# air_flow.net
KiCad netlist of a schematic drawn in EAGLE
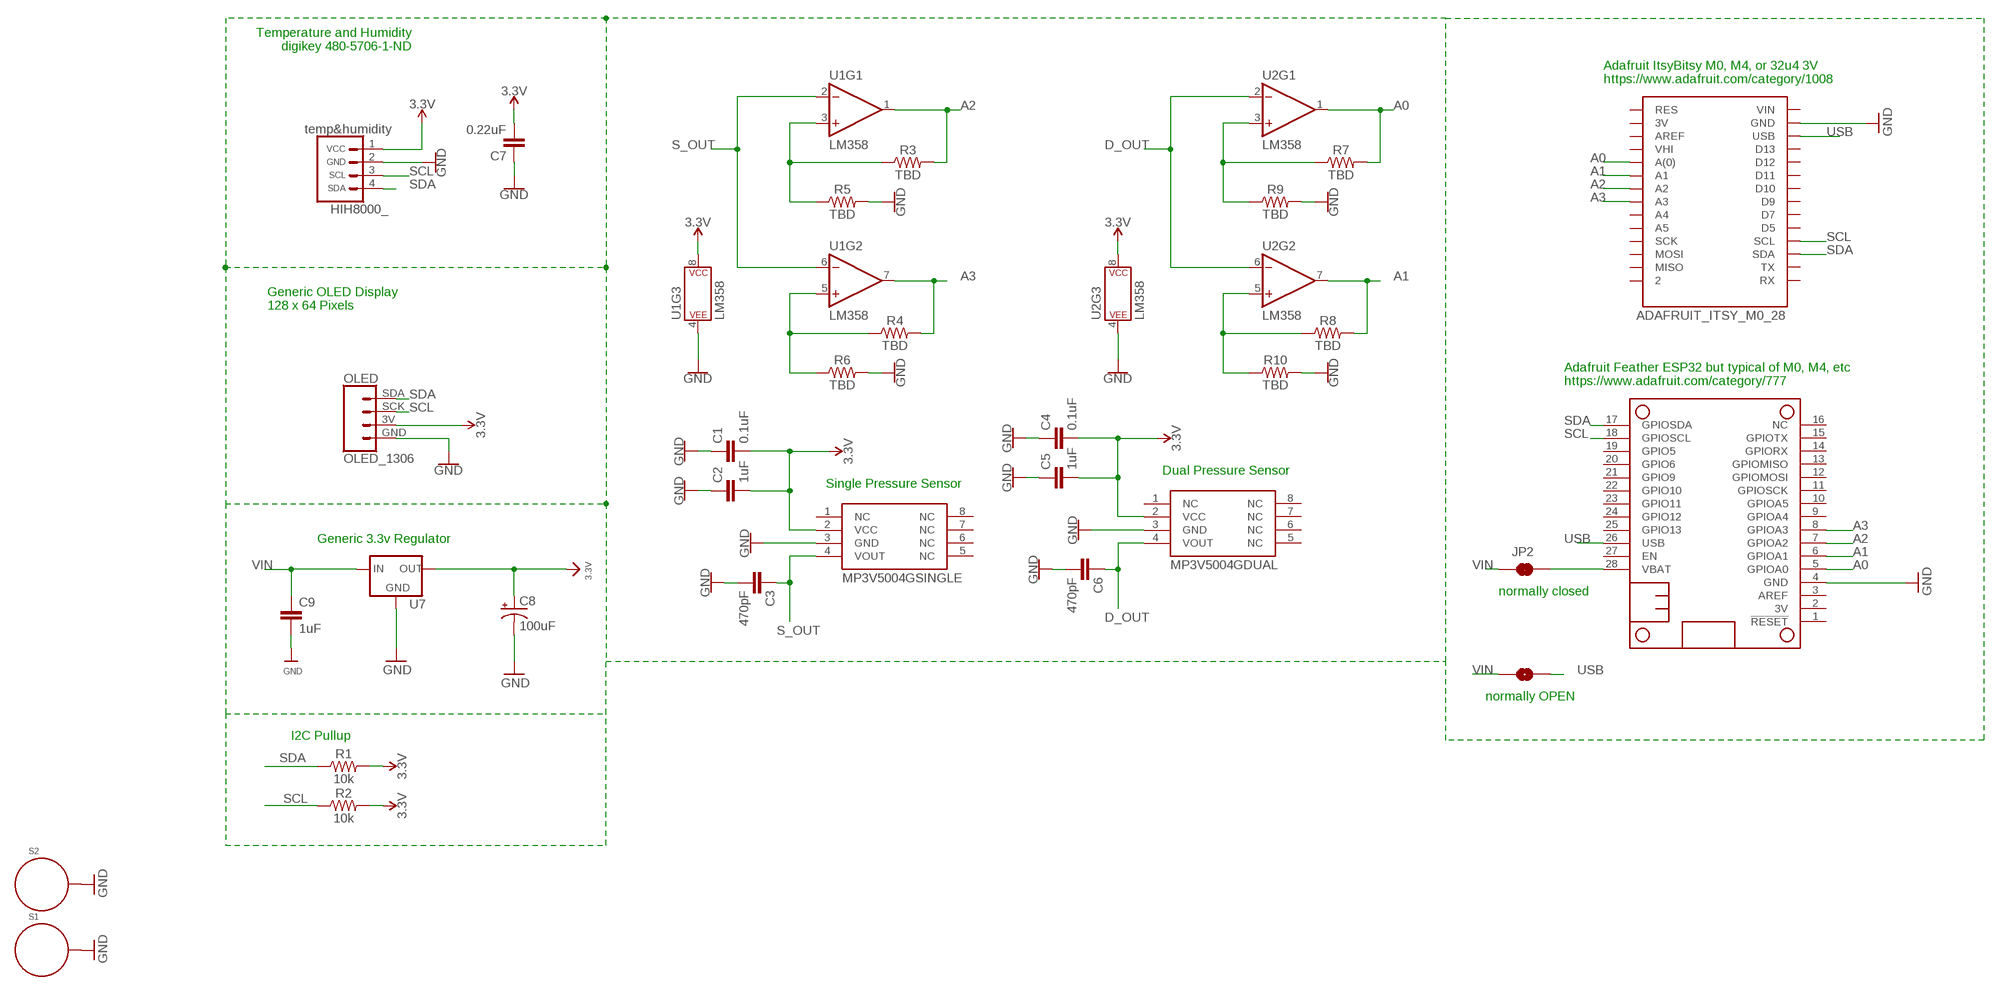
[diagram p0: schematic, sheet 1]

(export (version "E")
  (design (tool "Eeschema 10.0.6"))
  (components
    (comp (ref "C1")
      (value "0.1uF")
      (footprint "eagle-import:CAP-PTH-SMALL-KIT")
      (libsource (lib "eagle-import") (part "0.1UF-KIT-EZ-50V-20%"))
    )
    (comp (ref "C2")
      (value "1uF")
      (footprint "eagle-import:CAP-PTH-SMALL-KIT")
      (libsource (lib "eagle-import") (part "0.1UF-KIT-EZ-50V-20%"))
    )
    (comp (ref "C3")
      (value "470pF")
      (footprint "eagle-import:CAP-PTH-SMALL-KIT")
      (libsource (lib "eagle-import") (part "0.1UF-KIT-EZ-50V-20%"))
    )
    (comp (ref "C4")
      (value "0.1uF")
      (footprint "eagle-import:CAP-PTH-SMALL-KIT")
      (libsource (lib "eagle-import") (part "0.1UF-KIT-EZ-50V-20%"))
    )
    (comp (ref "C5")
      (value "1uF")
      (footprint "eagle-import:CAP-PTH-SMALL-KIT")
      (libsource (lib "eagle-import") (part "0.1UF-KIT-EZ-50V-20%"))
    )
    (comp (ref "C6")
      (value "470pF")
      (footprint "eagle-import:CAP-PTH-SMALL-KIT")
      (libsource (lib "eagle-import") (part "0.1UF-KIT-EZ-50V-20%"))
    )
    (comp (ref "C7")
      (value "0.22uF")
      (footprint "eagle-import:CAP-PTH-SMALL-KIT")
      (libsource (lib "eagle-import") (part "0.1UF-KIT-EZ-50V-20%"))
    )
    (comp (ref "C8")
      (value "100uF")
      (footprint "eagle-import:E3,5-8")
      (libsource (lib "eagle-import") (part "CPOL-USE3.5-8"))
    )
    (comp (ref "C9")
      (value "1uF")
      (footprint "eagle-import:CAP-PTH-SMALL-KIT")
      (libsource (lib "eagle-import") (part "0.1UF-KIT-EZ-50V-20%"))
    )
    (comp (ref "JP1")
      (value "JUMPER-SMT_2_NO_NO-SILK")
      (footprint "eagle-import:SMT-JUMPER_2_NO_NO-SILK")
      (libsource (lib "eagle-import") (part "JUMPER-SMT_2_NO_NO-SILK"))
    )
    (comp (ref "JP2")
      (value "JUMPER-SMT_2_NC_TRACE_SILK")
      (footprint "eagle-import:SMT-JUMPER_2_NC_TRACE_SILK")
      (libsource (lib "eagle-import") (part "JUMPER-SMT_2_NC_TRACE_SILK"))
    )
    (comp (ref "MS2")
      (value "FEATHERWING_NODIM")
      (footprint "eagle-import:FEATHERWING_DIM")
      (libsource (lib "eagle-import") (part "FEATHERWING_NODIM"))
    )
    (comp (ref "R1")
      (value "10k")
      (footprint "eagle-import:AXIAL-0.3")
      (libsource (lib "eagle-import") (part "10KOHM-HORIZ-1/4W-5%"))
    )
    (comp (ref "R2")
      (value "10k")
      (footprint "eagle-import:AXIAL-0.3")
      (libsource (lib "eagle-import") (part "10KOHM-HORIZ-1/4W-5%"))
    )
    (comp (ref "R3")
      (value "TBD")
      (footprint "eagle-import:AXIAL-0.3")
      (libsource (lib "eagle-import") (part "10KOHM-HORIZ-1/4W-5%"))
    )
    (comp (ref "R4")
      (value "TBD")
      (footprint "eagle-import:AXIAL-0.3")
      (libsource (lib "eagle-import") (part "10KOHM-HORIZ-1/4W-5%"))
    )
    (comp (ref "R5")
      (value "TBD")
      (footprint "eagle-import:AXIAL-0.3")
      (libsource (lib "eagle-import") (part "10KOHM-HORIZ-1/4W-5%"))
    )
    (comp (ref "R6")
      (value "TBD")
      (footprint "eagle-import:AXIAL-0.3")
      (libsource (lib "eagle-import") (part "10KOHM-HORIZ-1/4W-5%"))
    )
    (comp (ref "R7")
      (value "TBD")
      (footprint "eagle-import:AXIAL-0.3")
      (libsource (lib "eagle-import") (part "10KOHM-HORIZ-1/4W-5%"))
    )
    (comp (ref "R8")
      (value "TBD")
      (footprint "eagle-import:AXIAL-0.3")
      (libsource (lib "eagle-import") (part "10KOHM-HORIZ-1/4W-5%"))
    )
    (comp (ref "R9")
      (value "TBD")
      (footprint "eagle-import:AXIAL-0.3")
      (libsource (lib "eagle-import") (part "10KOHM-HORIZ-1/4W-5%"))
    )
    (comp (ref "R10")
      (value "TBD")
      (footprint "eagle-import:AXIAL-0.3")
      (libsource (lib "eagle-import") (part "10KOHM-HORIZ-1/4W-5%"))
    )
    (comp (ref "S1")
      (value "STANDOFF_ELECTRICAL5-32")
      (footprint "eagle-import:STANDOFF_ELECTRICAL_5_32")
      (libsource (lib "eagle-import") (part "STANDOFF_ELECTRICAL5-32"))
    )
    (comp (ref "S2")
      (value "STANDOFF_ELECTRICAL5-32")
      (footprint "eagle-import:STANDOFF_ELECTRICAL_5_32")
      (libsource (lib "eagle-import") (part "STANDOFF_ELECTRICAL5-32"))
    )
    (comp (ref "U$1")
      (value "OLED_1306")
      (footprint "eagle-import:OLED_1306")
      (libsource (lib "eagle-import") (part "OLED_1306"))
    )
    (comp (ref "U$2")
      (value "MP3V5004GSINGLE")
      (footprint "eagle-import:MP3V5004GP")
      (libsource (lib "eagle-import") (part "MP3V5004GSINGLE"))
    )
    (comp (ref "U$3")
      (value "MP3V5004GDUAL")
      (footprint "eagle-import:MP3V5004DP")
      (libsource (lib "eagle-import") (part "MP3V5004GDUAL"))
    )
    (comp (ref "U$4")
      (value "HIH8000_")
      (footprint "eagle-import:HIH8120_TH")
      (libsource (lib "eagle-import") (part "HIH8000_"))
    )
    (comp (ref "U$45")
      (value "ADAFRUIT_ITSY_M0_28")
      (footprint "eagle-import:ADAFRUIT_ITS_MO_28")
      (libsource (lib "eagle-import") (part "ADAFRUIT_ITSY_M0_28"))
    )
    (comp (ref "U1")
      (value "LM358")
      (footprint "eagle-import:DIP08")
      (libsource (lib "eagle-import") (part "LM358"))
    )
    (comp (ref "U2")
      (value "LM358")
      (footprint "eagle-import:DIP08")
      (libsource (lib "eagle-import") (part "LM358"))
    )
    (comp (ref "U7")
      (value "V_REG_78XXSINK")
      (footprint "eagle-import:TO220-IGO")
      (libsource (lib "eagle-import") (part "V_REG_78XXSINK"))
    )
  )
  (nets
    (net (code "1") (name "/3V") (class "Default")
      (node (ref "MS2") (pin "2") (pinfunction "3V_2") (pintype "power_in"))
    )
    (net (code "2") (name "/A0") (class "Default")
      (node (ref "MS2") (pin "5") (pinfunction "GPIOA0_5") (pintype "bidirectional"))
      (node (ref "R7") (pin "P$2") (pinfunction "2_P$2") (pintype "passive"))
      (node (ref "U$45") (pin "A0") (pinfunction "A(0)_A0") (pintype "bidirectional"))
      (node (ref "U2") (pin "1") (pinfunction "OUT_1") (pintype "output"))
    )
    (net (code "3") (name "/A1") (class "Default")
      (node (ref "MS2") (pin "6") (pinfunction "GPIOA1_6") (pintype "bidirectional"))
      (node (ref "R8") (pin "P$2") (pinfunction "2_P$2") (pintype "passive"))
      (node (ref "U$45") (pin "A1") (pinfunction "A1_A1") (pintype "bidirectional"))
      (node (ref "U2") (pin "7") (pinfunction "OUT_7") (pintype "output"))
    )
    (net (code "4") (name "/A2") (class "Default")
      (node (ref "MS2") (pin "7") (pinfunction "GPIOA2_7") (pintype "bidirectional"))
      (node (ref "R3") (pin "P$2") (pinfunction "2_P$2") (pintype "passive"))
      (node (ref "U$45") (pin "A2") (pinfunction "A2_A2") (pintype "bidirectional"))
      (node (ref "U1") (pin "1") (pinfunction "OUT_1") (pintype "output"))
    )
    (net (code "5") (name "/A3") (class "Default")
      (node (ref "MS2") (pin "8") (pinfunction "GPIOA3_8") (pintype "bidirectional"))
      (node (ref "R4") (pin "P$2") (pinfunction "2_P$2") (pintype "passive"))
      (node (ref "U$45") (pin "A3") (pinfunction "A3_A3") (pintype "bidirectional"))
      (node (ref "U1") (pin "7") (pinfunction "OUT_7") (pintype "output"))
    )
    (net (code "6") (name "/D_OUT") (class "Default")
      (node (ref "C6") (pin "1") (pinfunction "1_1") (pintype "passive"))
      (node (ref "U$3") (pin "4") (pinfunction "VOUT_4") (pintype "bidirectional"))
      (node (ref "U2") (pin "2") (pinfunction "-IN_2") (pintype "input"))
      (node (ref "U2") (pin "6") (pinfunction "-IN_6") (pintype "input"))
    )
    (net (code "7") (name "/SCL") (class "Default")
      (node (ref "MS2") (pin "18") (pinfunction "GPIOSCL_18") (pintype "bidirectional"))
      (node (ref "R2") (pin "P$1") (pinfunction "1_P$1") (pintype "passive"))
      (node (ref "U$1") (pin "SCK") (pinfunction "SCK_SCK") (pintype "passive"))
      (node (ref "U$4") (pin "3") (pinfunction "SCL_3") (pintype "power_in"))
      (node (ref "U$45") (pin "SCL") (pinfunction "SCL_SCL") (pintype "bidirectional"))
    )
    (net (code "8") (name "/SDA") (class "Default")
      (node (ref "MS2") (pin "17") (pinfunction "GPIOSDA_17") (pintype "bidirectional"))
      (node (ref "R1") (pin "P$1") (pinfunction "1_P$1") (pintype "passive"))
      (node (ref "U$1") (pin "SDA") (pinfunction "SDA_SDA") (pintype "passive"))
      (node (ref "U$4") (pin "4") (pinfunction "SDA_4") (pintype "passive"))
      (node (ref "U$45") (pin "SDA") (pinfunction "SDA_SDA") (pintype "bidirectional"))
    )
    (net (code "9") (name "/S_OUT") (class "Default")
      (node (ref "C3") (pin "1") (pinfunction "1_1") (pintype "passive"))
      (node (ref "U$2") (pin "4") (pinfunction "VOUT_4") (pintype "bidirectional"))
      (node (ref "U1") (pin "2") (pinfunction "-IN_2") (pintype "input"))
      (node (ref "U1") (pin "6") (pinfunction "-IN_6") (pintype "input"))
    )
    (net (code "10") (name "/USB") (class "Default")
      (node (ref "JP1") (pin "2") (pinfunction "2_2") (pintype "passive"))
      (node (ref "MS2") (pin "26") (pinfunction "USB_26") (pintype "power_in"))
      (node (ref "U$45") (pin "USB") (pinfunction "USB_USB") (pintype "bidirectional"))
    )
    (net (code "11") (name "/VIN") (class "Default")
      (node (ref "C9") (pin "1") (pinfunction "1_1") (pintype "passive"))
      (node (ref "JP2") (pin "1") (pinfunction "1_1") (pintype "passive"))
      (node (ref "U7") (pin "IN") (pinfunction "IN_IN") (pintype "input"))
    )
    (net (code "12") (name "3.3V") (class "Default")
      (node (ref "C1") (pin "2") (pinfunction "2_2") (pintype "passive"))
      (node (ref "C2") (pin "2") (pinfunction "2_2") (pintype "passive"))
      (node (ref "C4") (pin "2") (pinfunction "2_2") (pintype "passive"))
      (node (ref "C5") (pin "2") (pinfunction "2_2") (pintype "passive"))
      (node (ref "C7") (pin "2") (pinfunction "2_2") (pintype "passive"))
      (node (ref "C8") (pin "+") (pinfunction "+_+") (pintype "passive"))
      (node (ref "R1") (pin "P$2") (pinfunction "2_P$2") (pintype "passive"))
      (node (ref "R2") (pin "P$2") (pinfunction "2_P$2") (pintype "passive"))
      (node (ref "U$1") (pin "3V") (pinfunction "VCC_3V") (pintype "power_in"))
      (node (ref "U$2") (pin "2") (pinfunction "VCC_2") (pintype "bidirectional"))
      (node (ref "U$3") (pin "2") (pinfunction "VCC_2") (pintype "bidirectional"))
      (node (ref "U$4") (pin "1") (pinfunction "VCC_1") (pintype "passive"))
      (node (ref "U1") (pin "8") (pinfunction "P$V+_8") (pintype "bidirectional"))
      (node (ref "U2") (pin "8") (pinfunction "P$V+_8") (pintype "bidirectional"))
      (node (ref "U7") (pin "OUT") (pinfunction "OUT_OUT") (pintype "passive"))
    )
    (net (code "13") (name "GND") (class "Default")
      (node (ref "C1") (pin "1") (pinfunction "1_1") (pintype "passive"))
      (node (ref "C2") (pin "1") (pinfunction "1_1") (pintype "passive"))
      (node (ref "C3") (pin "2") (pinfunction "2_2") (pintype "passive"))
      (node (ref "C4") (pin "1") (pinfunction "1_1") (pintype "passive"))
      (node (ref "C5") (pin "1") (pinfunction "1_1") (pintype "passive"))
      (node (ref "C6") (pin "2") (pinfunction "2_2") (pintype "passive"))
      (node (ref "C7") (pin "1") (pinfunction "1_1") (pintype "passive"))
      (node (ref "C8") (pin "-") (pinfunction "-_-") (pintype "passive"))
      (node (ref "C9") (pin "2") (pinfunction "2_2") (pintype "passive"))
      (node (ref "MS2") (pin "4") (pinfunction "GND_4") (pintype "power_in"))
      (node (ref "R10") (pin "P$2") (pinfunction "2_P$2") (pintype "passive"))
      (node (ref "R5") (pin "P$2") (pinfunction "2_P$2") (pintype "passive"))
      (node (ref "R6") (pin "P$2") (pinfunction "2_P$2") (pintype "passive"))
      (node (ref "R9") (pin "P$2") (pinfunction "2_P$2") (pintype "passive"))
      (node (ref "S1") (pin "P1") (pinfunction "P$1_P1") (pintype "bidirectional"))
      (node (ref "S2") (pin "P1") (pinfunction "P$1_P1") (pintype "bidirectional"))
      (node (ref "U$1") (pin "GND") (pinfunction "GND_GND") (pintype "passive"))
      (node (ref "U$2") (pin "3") (pinfunction "GND_3") (pintype "bidirectional"))
      (node (ref "U$3") (pin "3") (pinfunction "GND_3") (pintype "bidirectional"))
      (node (ref "U$4") (pin "2") (pinfunction "GND_2") (pintype "passive"))
      (node (ref "U$45") (pin "GND") (pinfunction "GND_GND") (pintype "bidirectional"))
      (node (ref "U1") (pin "4") (pinfunction "P$V-_4") (pintype "bidirectional"))
      (node (ref "U2") (pin "4") (pinfunction "P$V-_4") (pintype "bidirectional"))
      (node (ref "U7") (pin "GND") (pinfunction "GND_GND") (pintype "input"))
    )
    (net (code "14") (name "Net-(MS2-VBAT)") (class "Default")
      (node (ref "JP2") (pin "2") (pinfunction "2_2") (pintype "passive"))
      (node (ref "MS2") (pin "28") (pinfunction "VBAT_28") (pintype "power_in"))
    )
    (net (code "15") (name "Net-(R3-1)") (class "Default")
      (node (ref "R3") (pin "P$1") (pinfunction "1_P$1") (pintype "passive"))
      (node (ref "R5") (pin "P$1") (pinfunction "1_P$1") (pintype "passive"))
      (node (ref "U1") (pin "3") (pinfunction "+IN_3") (pintype "input"))
    )
    (net (code "16") (name "Net-(R4-1)") (class "Default")
      (node (ref "R4") (pin "P$1") (pinfunction "1_P$1") (pintype "passive"))
      (node (ref "R6") (pin "P$1") (pinfunction "1_P$1") (pintype "passive"))
      (node (ref "U1") (pin "5") (pinfunction "+IN_5") (pintype "input"))
    )
    (net (code "17") (name "Net-(R7-1)") (class "Default")
      (node (ref "R7") (pin "P$1") (pinfunction "1_P$1") (pintype "passive"))
      (node (ref "R9") (pin "P$1") (pinfunction "1_P$1") (pintype "passive"))
      (node (ref "U2") (pin "3") (pinfunction "+IN_3") (pintype "input"))
    )
    (net (code "18") (name "Net-(R10-1)") (class "Default")
      (node (ref "R10") (pin "P$1") (pinfunction "1_P$1") (pintype "passive"))
      (node (ref "R8") (pin "P$1") (pinfunction "1_P$1") (pintype "passive"))
      (node (ref "U2") (pin "5") (pinfunction "+IN_5") (pintype "input"))
    )
    (net (code "19") (name "unconnected-(JP1-Pad1)") (class "Default")
      (node (ref "JP1") (pin "1") (pinfunction "1_1") (pintype "passive"))
    )
    (net (code "20") (name "unconnected-(MS2-AREF-Pad3)") (class "Default")
      (node (ref "MS2") (pin "3") (pinfunction "AREF_3") (pintype "passive"))
    )
    (net (code "21") (name "unconnected-(MS2-EN-Pad27)") (class "Default")
      (node (ref "MS2") (pin "27") (pinfunction "EN_27") (pintype "passive"))
    )
    (net (code "22") (name "unconnected-(MS2-GPIO5-Pad19)") (class "Default")
      (node (ref "MS2") (pin "19") (pinfunction "GPIO5_19") (pintype "bidirectional"))
    )
    (net (code "23") (name "unconnected-(MS2-GPIO6-Pad20)") (class "Default")
      (node (ref "MS2") (pin "20") (pinfunction "GPIO6_20") (pintype "bidirectional"))
    )
    (net (code "24") (name "unconnected-(MS2-GPIO9-Pad21)") (class "Default")
      (node (ref "MS2") (pin "21") (pinfunction "GPIO9_21") (pintype "bidirectional"))
    )
    (net (code "25") (name "unconnected-(MS2-GPIO10-Pad22)") (class "Default")
      (node (ref "MS2") (pin "22") (pinfunction "GPIO10_22") (pintype "bidirectional"))
    )
    (net (code "26") (name "unconnected-(MS2-GPIO11-Pad23)") (class "Default")
      (node (ref "MS2") (pin "23") (pinfunction "GPIO11_23") (pintype "bidirectional"))
    )
    (net (code "27") (name "unconnected-(MS2-GPIO12-Pad24)") (class "Default")
      (node (ref "MS2") (pin "24") (pinfunction "GPIO12_24") (pintype "bidirectional"))
    )
    (net (code "28") (name "unconnected-(MS2-GPIO13-Pad25)") (class "Default")
      (node (ref "MS2") (pin "25") (pinfunction "GPIO13_25") (pintype "bidirectional"))
    )
    (net (code "29") (name "unconnected-(MS2-GPIOA4-Pad9)") (class "Default")
      (node (ref "MS2") (pin "9") (pinfunction "GPIOA4_9") (pintype "bidirectional"))
    )
    (net (code "30") (name "unconnected-(MS2-GPIOA5-Pad10)") (class "Default")
      (node (ref "MS2") (pin "10") (pinfunction "GPIOA5_10") (pintype "bidirectional"))
    )
    (net (code "31") (name "unconnected-(MS2-GPIOMISO-Pad13)") (class "Default")
      (node (ref "MS2") (pin "13") (pinfunction "GPIOMISO_13") (pintype "bidirectional"))
    )
    (net (code "32") (name "unconnected-(MS2-GPIOMOSI-Pad12)") (class "Default")
      (node (ref "MS2") (pin "12") (pinfunction "GPIOMOSI_12") (pintype "bidirectional"))
    )
    (net (code "33") (name "unconnected-(MS2-GPIORX-Pad14)") (class "Default")
      (node (ref "MS2") (pin "14") (pinfunction "GPIORX_14") (pintype "bidirectional"))
    )
    (net (code "34") (name "unconnected-(MS2-GPIOSCK-Pad11)") (class "Default")
      (node (ref "MS2") (pin "11") (pinfunction "GPIOSCK_11") (pintype "bidirectional"))
    )
    (net (code "35") (name "unconnected-(MS2-GPIOTX-Pad15)") (class "Default")
      (node (ref "MS2") (pin "15") (pinfunction "GPIOTX_15") (pintype "bidirectional"))
    )
    (net (code "36") (name "unconnected-(MS2-NC-Pad16)") (class "Default")
      (node (ref "MS2") (pin "16") (pinfunction "NC_16") (pintype "passive"))
    )
    (net (code "37") (name "unconnected-(MS2-~{RESET}-Pad1)") (class "Default")
      (node (ref "MS2") (pin "1") (pinfunction "~{RESET}_1") (pintype "input"))
    )
    (net (code "38") (name "unconnected-(U$2-NC-Pad1)") (class "Default")
      (node (ref "U$2") (pin "1") (pinfunction "NC_1") (pintype "bidirectional"))
    )
    (net (code "39") (name "unconnected-(U$2-NC-Pad5)") (class "Default")
      (node (ref "U$2") (pin "5") (pinfunction "NC_5") (pintype "bidirectional"))
    )
    (net (code "40") (name "unconnected-(U$2-NC-Pad6)") (class "Default")
      (node (ref "U$2") (pin "6") (pinfunction "NC_6") (pintype "bidirectional"))
    )
    (net (code "41") (name "unconnected-(U$2-NC-Pad7)") (class "Default")
      (node (ref "U$2") (pin "7") (pinfunction "NC_7") (pintype "bidirectional"))
    )
    (net (code "42") (name "unconnected-(U$2-NC-Pad8)") (class "Default")
      (node (ref "U$2") (pin "8") (pinfunction "NC_8") (pintype "bidirectional"))
    )
    (net (code "43") (name "unconnected-(U$3-NC-Pad1)") (class "Default")
      (node (ref "U$3") (pin "1") (pinfunction "NC_1") (pintype "bidirectional"))
    )
    (net (code "44") (name "unconnected-(U$3-NC-Pad5)") (class "Default")
      (node (ref "U$3") (pin "5") (pinfunction "NC_5") (pintype "bidirectional"))
    )
    (net (code "45") (name "unconnected-(U$3-NC-Pad6)") (class "Default")
      (node (ref "U$3") (pin "6") (pinfunction "NC_6") (pintype "bidirectional"))
    )
    (net (code "46") (name "unconnected-(U$3-NC-Pad7)") (class "Default")
      (node (ref "U$3") (pin "7") (pinfunction "NC_7") (pintype "bidirectional"))
    )
    (net (code "47") (name "unconnected-(U$3-NC-Pad8)") (class "Default")
      (node (ref "U$3") (pin "8") (pinfunction "NC_8") (pintype "bidirectional"))
    )
    (net (code "48") (name "unconnected-(U$45-Pad2)") (class "Default")
      (node (ref "U$45") (pin "2") (pinfunction "2_2") (pintype "bidirectional"))
    )
    (net (code "49") (name "unconnected-(U$45-Pad3V)") (class "Default")
      (node (ref "U$45") (pin "3V") (pinfunction "3V_3V") (pintype "bidirectional"))
    )
    (net (code "50") (name "unconnected-(U$45-PadA4)") (class "Default")
      (node (ref "U$45") (pin "A4") (pinfunction "A4_A4") (pintype "bidirectional"))
    )
    (net (code "51") (name "unconnected-(U$45-PadA5)") (class "Default")
      (node (ref "U$45") (pin "A5") (pinfunction "A5_A5") (pintype "bidirectional"))
    )
    (net (code "52") (name "unconnected-(U$45-PadAREF)") (class "Default")
      (node (ref "U$45") (pin "AREF") (pinfunction "AREF_AREF") (pintype "bidirectional"))
    )
    (net (code "53") (name "unconnected-(U$45-PadD5)") (class "Default")
      (node (ref "U$45") (pin "D5") (pinfunction "D5_D5") (pintype "bidirectional"))
    )
    (net (code "54") (name "unconnected-(U$45-PadD7)") (class "Default")
      (node (ref "U$45") (pin "D7") (pinfunction "D7_D7") (pintype "bidirectional"))
    )
    (net (code "55") (name "unconnected-(U$45-PadD9)") (class "Default")
      (node (ref "U$45") (pin "D9") (pinfunction "D9_D9") (pintype "bidirectional"))
    )
    (net (code "56") (name "unconnected-(U$45-PadD10)") (class "Default")
      (node (ref "U$45") (pin "D10") (pinfunction "D10_D10") (pintype "bidirectional"))
    )
    (net (code "57") (name "unconnected-(U$45-PadD11)") (class "Default")
      (node (ref "U$45") (pin "D11") (pinfunction "D11_D11") (pintype "bidirectional"))
    )
    (net (code "58") (name "unconnected-(U$45-PadD12)") (class "Default")
      (node (ref "U$45") (pin "D12") (pinfunction "D12_D12") (pintype "bidirectional"))
    )
    (net (code "59") (name "unconnected-(U$45-PadD13)") (class "Default")
      (node (ref "U$45") (pin "D13") (pinfunction "D13_D13") (pintype "bidirectional"))
    )
    (net (code "60") (name "unconnected-(U$45-PadMISO)") (class "Default")
      (node (ref "U$45") (pin "MISO") (pinfunction "MISO_MISO") (pintype "bidirectional"))
    )
    (net (code "61") (name "unconnected-(U$45-PadMOSI)") (class "Default")
      (node (ref "U$45") (pin "MOSI") (pinfunction "MOSI_MOSI") (pintype "bidirectional"))
    )
    (net (code "62") (name "unconnected-(U$45-PadRES)") (class "Default")
      (node (ref "U$45") (pin "RES") (pinfunction "RES_RES") (pintype "bidirectional"))
    )
    (net (code "63") (name "unconnected-(U$45-PadRX)") (class "Default")
      (node (ref "U$45") (pin "RX") (pinfunction "RX_RX") (pintype "bidirectional"))
    )
    (net (code "64") (name "unconnected-(U$45-PadSCK)") (class "Default")
      (node (ref "U$45") (pin "SCK") (pinfunction "SCK_SCK") (pintype "bidirectional"))
    )
    (net (code "65") (name "unconnected-(U$45-PadTX)") (class "Default")
      (node (ref "U$45") (pin "TX") (pinfunction "TX_TX") (pintype "bidirectional"))
    )
    (net (code "66") (name "unconnected-(U$45-PadVHI)") (class "Default")
      (node (ref "U$45") (pin "VHI") (pinfunction "VHI_VHI") (pintype "bidirectional"))
    )
    (net (code "67") (name "unconnected-(U$45-PadVIN)") (class "Default")
      (node (ref "U$45") (pin "VIN") (pinfunction "VIN_VIN") (pintype "bidirectional"))
    )
  )
)
